# Stepper-Driver.net
KiCad netlist of a schematic drawn in EAGLE
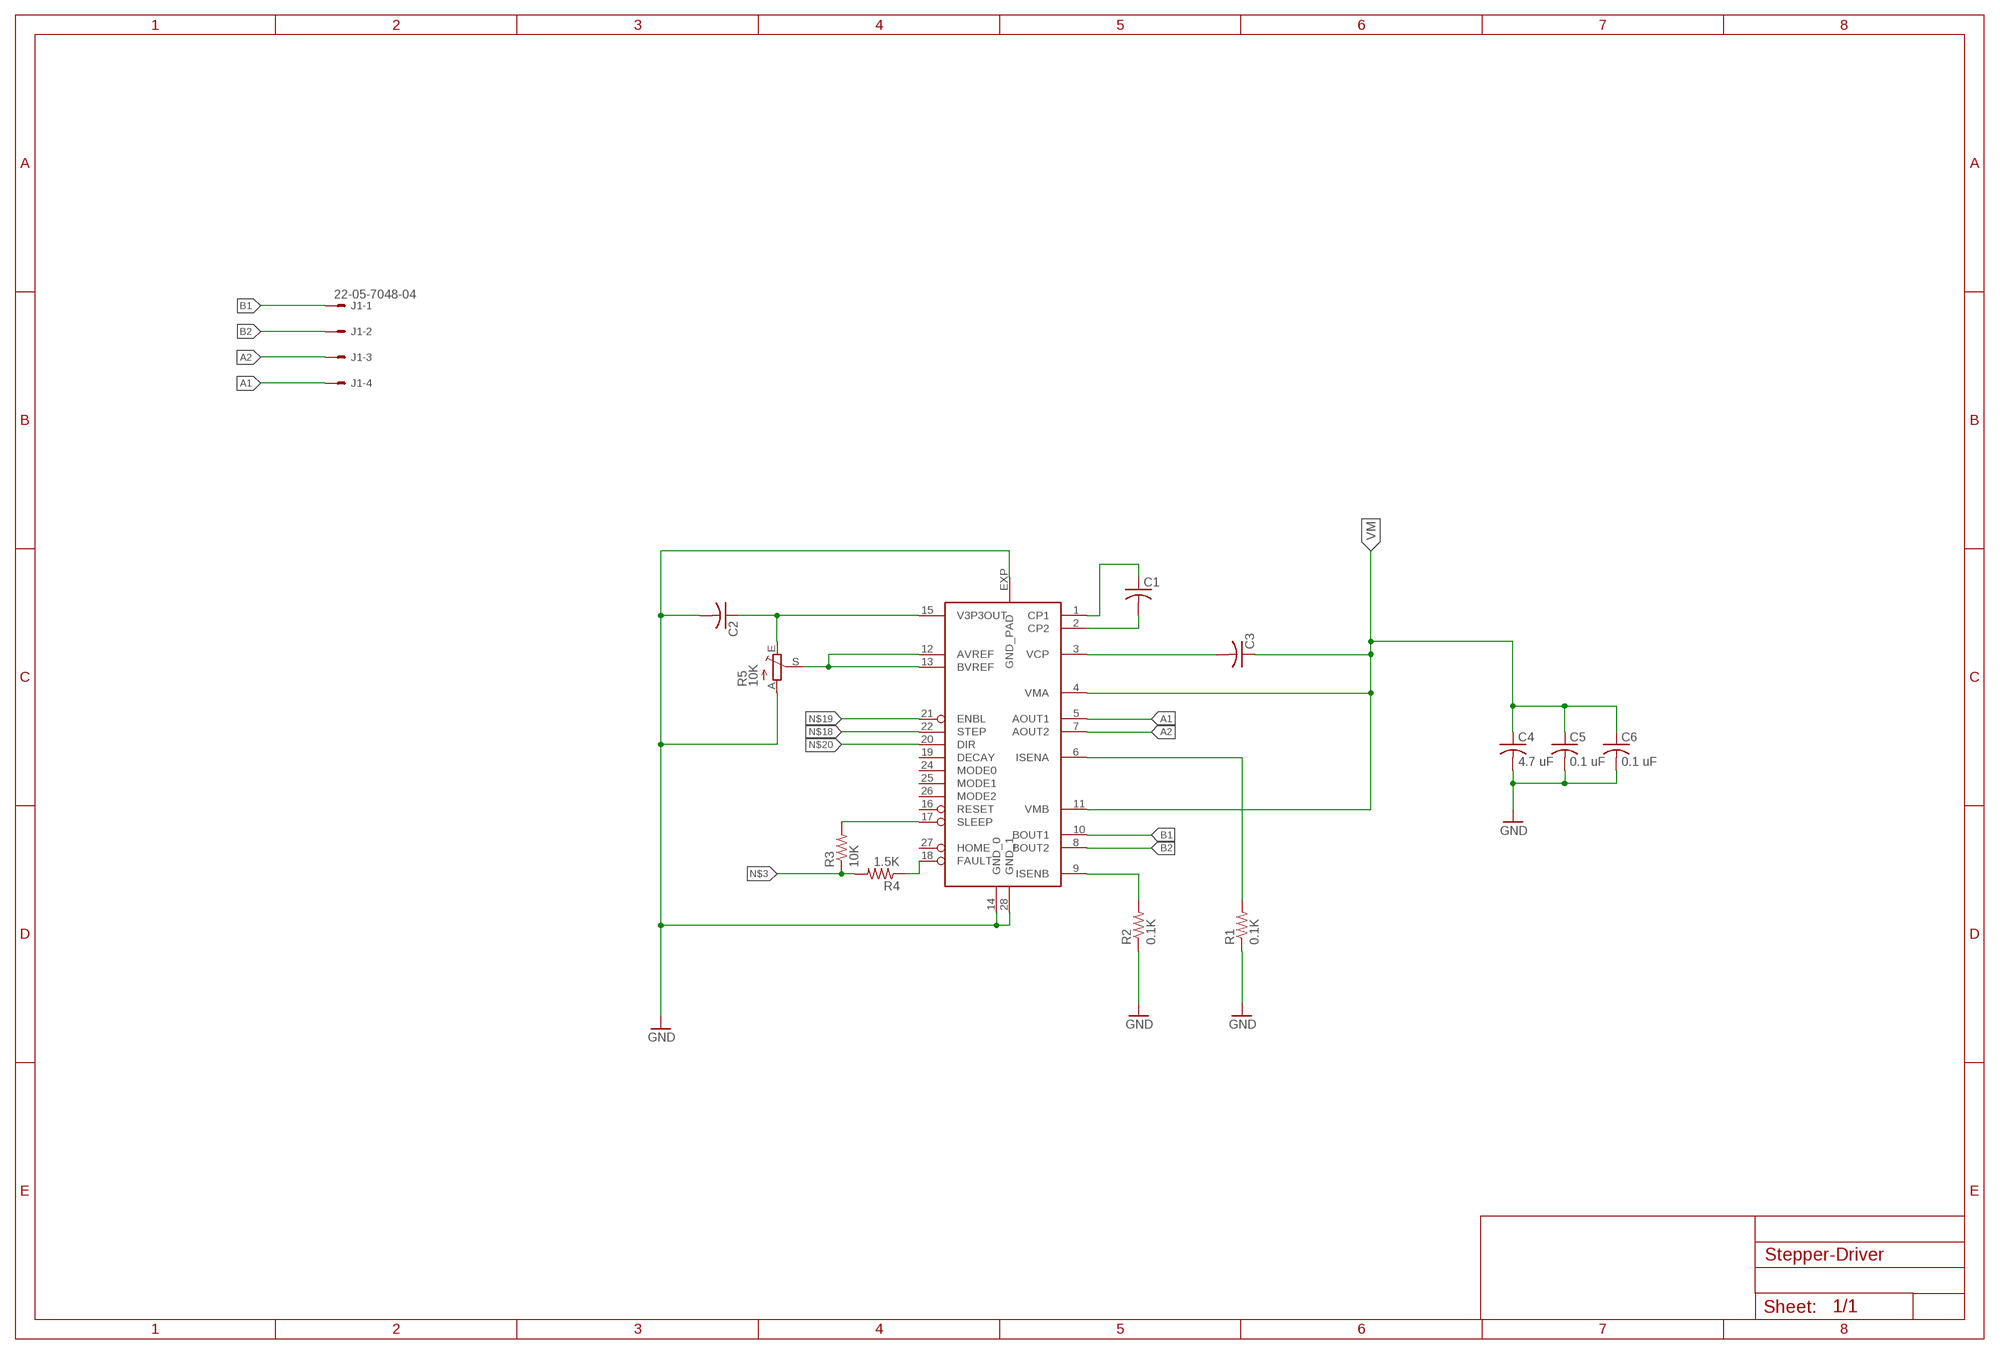
[diagram p0: schematic, sheet 1]

(export (version "E")
  (design (tool "Eeschema 10.0.6"))
  (components
    (comp (ref "C1")
      (value "C-USC0805")
      (footprint "eagle-import:C0805")
      (libsource (lib "eagle-import") (part "C-USC0805"))
    )
    (comp (ref "C2")
      (value "C-USC0805")
      (footprint "eagle-import:C0805")
      (libsource (lib "eagle-import") (part "C-USC0805"))
    )
    (comp (ref "C3")
      (value "C-USC0805")
      (footprint "eagle-import:C0805")
      (libsource (lib "eagle-import") (part "C-USC0805"))
    )
    (comp (ref "C4")
      (value "4.7 uF")
      (footprint "eagle-import:C0805")
      (libsource (lib "eagle-import") (part "C-USC0805"))
    )
    (comp (ref "C5")
      (value "0.1 uF")
      (footprint "eagle-import:C0805")
      (libsource (lib "eagle-import") (part "C-USC0805"))
    )
    (comp (ref "C6")
      (value "0.1 uF")
      (footprint "eagle-import:C0805")
      (libsource (lib "eagle-import") (part "C-USC0805"))
    )
    (comp (ref "J1")
      (value "22-05-7048-04")
      (footprint "eagle-import:7395-04")
      (libsource (lib "eagle-import") (part "22-?-0405-7048"))
    )
    (comp (ref "R1")
      (value "0.1K")
      (footprint "eagle-import:R0805")
      (libsource (lib "eagle-import") (part "R-US_R0805"))
    )
    (comp (ref "R2")
      (value "0.1K")
      (footprint "eagle-import:R0805")
      (libsource (lib "eagle-import") (part "R-US_R0805"))
    )
    (comp (ref "R3")
      (value "10K")
      (footprint "eagle-import:R0805")
      (libsource (lib "eagle-import") (part "R-US_R0805"))
    )
    (comp (ref "R4")
      (value "1.5K")
      (footprint "eagle-import:R0805")
      (libsource (lib "eagle-import") (part "R-US_R0805"))
    )
    (comp (ref "R5")
      (value "10K")
      (footprint "eagle-import:CT6")
      (libsource (lib "eagle-import") (part "TRIM_EU-CT6"))
    )
    (comp (ref "U$1")
      (value "DRV8825PWP")
      (footprint "eagle-import:TSSOP-28")
      (libsource (lib "eagle-import") (part "DRV8825PWP"))
    )
  )
  (nets
    (net (code "1") (name "A1") (class "Default")
      (node (ref "J1") (pin "4") (pinfunction "S_4") (pintype "passive"))
      (node (ref "U$1") (pin "5") (pinfunction "AOUT1_5") (pintype "output"))
    )
    (net (code "2") (name "A2") (class "Default")
      (node (ref "J1") (pin "3") (pinfunction "S_3") (pintype "passive"))
      (node (ref "U$1") (pin "7") (pinfunction "AOUT2_7") (pintype "output"))
    )
    (net (code "3") (name "B1") (class "Default")
      (node (ref "J1") (pin "1") (pinfunction "S_1") (pintype "passive"))
      (node (ref "U$1") (pin "10") (pinfunction "BOUT1_10") (pintype "output"))
    )
    (net (code "4") (name "B2") (class "Default")
      (node (ref "J1") (pin "2") (pinfunction "S_2") (pintype "passive"))
      (node (ref "U$1") (pin "8") (pinfunction "BOUT2_8") (pintype "output"))
    )
    (net (code "5") (name "GND") (class "Default")
      (node (ref "C2") (pin "2") (pinfunction "2_2") (pintype "passive"))
      (node (ref "C4") (pin "2") (pinfunction "2_2") (pintype "passive"))
      (node (ref "C5") (pin "2") (pinfunction "2_2") (pintype "passive"))
      (node (ref "C6") (pin "2") (pinfunction "2_2") (pintype "passive"))
      (node (ref "R1") (pin "1") (pinfunction "1_1") (pintype "passive"))
      (node (ref "R2") (pin "1") (pinfunction "1_1") (pintype "passive"))
      (node (ref "R5") (pin "A") (pinfunction "A_A") (pintype "passive"))
      (node (ref "U$1") (pin "14") (pinfunction "GND_0_14") (pintype "power_in"))
      (node (ref "U$1") (pin "28") (pinfunction "GND_1_28") (pintype "power_in"))
      (node (ref "U$1") (pin "EXP") (pinfunction "GND_PAD_EXP") (pintype "power_in"))
    )
    (net (code "6") (name "N$3") (class "Default")
      (node (ref "R3") (pin "1") (pinfunction "1_1") (pintype "passive"))
      (node (ref "R4") (pin "2") (pinfunction "2_2") (pintype "passive"))
    )
    (net (code "7") (name "N$18") (class "Default")
      (node (ref "U$1") (pin "22") (pinfunction "STEP_22") (pintype "input"))
    )
    (net (code "8") (name "N$19") (class "Default")
      (node (ref "U$1") (pin "21") (pinfunction "ENBL_21") (pintype "input"))
    )
    (net (code "9") (name "N$20") (class "Default")
      (node (ref "U$1") (pin "20") (pinfunction "DIR_20") (pintype "input"))
    )
    (net (code "10") (name "Net-(U$1-AVREF)") (class "Default")
      (node (ref "R5") (pin "S") (pinfunction "S_S") (pintype "passive"))
      (node (ref "U$1") (pin "12") (pinfunction "AVREF_12") (pintype "input"))
      (node (ref "U$1") (pin "13") (pinfunction "BVREF_13") (pintype "input"))
    )
    (net (code "11") (name "Net-(U$1-CP1)") (class "Default")
      (node (ref "C1") (pin "1") (pinfunction "1_1") (pintype "passive"))
      (node (ref "U$1") (pin "1") (pinfunction "CP1_1") (pintype "bidirectional"))
    )
    (net (code "12") (name "Net-(U$1-CP2)") (class "Default")
      (node (ref "C1") (pin "2") (pinfunction "2_2") (pintype "passive"))
      (node (ref "U$1") (pin "2") (pinfunction "CP2_2") (pintype "bidirectional"))
    )
    (net (code "13") (name "Net-(U$1-FAULT)") (class "Default")
      (node (ref "R4") (pin "1") (pinfunction "1_1") (pintype "passive"))
      (node (ref "U$1") (pin "18") (pinfunction "FAULT_18") (pintype "output"))
    )
    (net (code "14") (name "Net-(U$1-ISENA)") (class "Default")
      (node (ref "R1") (pin "2") (pinfunction "2_2") (pintype "passive"))
      (node (ref "U$1") (pin "6") (pinfunction "ISENA_6") (pintype "output"))
    )
    (net (code "15") (name "Net-(U$1-ISENB)") (class "Default")
      (node (ref "R2") (pin "2") (pinfunction "2_2") (pintype "passive"))
      (node (ref "U$1") (pin "9") (pinfunction "ISENB_9") (pintype "output"))
    )
    (net (code "16") (name "Net-(U$1-SLEEP)") (class "Default")
      (node (ref "R3") (pin "2") (pinfunction "2_2") (pintype "passive"))
      (node (ref "U$1") (pin "17") (pinfunction "SLEEP_17") (pintype "input"))
    )
    (net (code "17") (name "Net-(U$1-V3P3OUT)") (class "Default")
      (node (ref "C2") (pin "1") (pinfunction "1_1") (pintype "passive"))
      (node (ref "R5") (pin "E") (pinfunction "E_E") (pintype "passive"))
      (node (ref "U$1") (pin "15") (pinfunction "V3P3OUT_15") (pintype "output"))
    )
    (net (code "18") (name "Net-(U$1-VCP)") (class "Default")
      (node (ref "C3") (pin "2") (pinfunction "2_2") (pintype "passive"))
      (node (ref "U$1") (pin "3") (pinfunction "VCP_3") (pintype "bidirectional"))
    )
    (net (code "19") (name "VM") (class "Default")
      (node (ref "C3") (pin "1") (pinfunction "1_1") (pintype "passive"))
      (node (ref "C4") (pin "1") (pinfunction "1_1") (pintype "passive"))
      (node (ref "C5") (pin "1") (pinfunction "1_1") (pintype "passive"))
      (node (ref "C6") (pin "1") (pinfunction "1_1") (pintype "passive"))
      (node (ref "U$1") (pin "11") (pinfunction "VMB_11") (pintype "power_in"))
      (node (ref "U$1") (pin "4") (pinfunction "VMA_4") (pintype "power_in"))
    )
    (net (code "20") (name "unconnected-(U$1-DECAY-Pad19)") (class "Default")
      (node (ref "U$1") (pin "19") (pinfunction "DECAY_19") (pintype "input"))
    )
    (net (code "21") (name "unconnected-(U$1-HOME-Pad27)") (class "Default")
      (node (ref "U$1") (pin "27") (pinfunction "HOME_27") (pintype "output"))
    )
    (net (code "22") (name "unconnected-(U$1-MODE0-Pad24)") (class "Default")
      (node (ref "U$1") (pin "24") (pinfunction "MODE0_24") (pintype "input"))
    )
    (net (code "23") (name "unconnected-(U$1-MODE1-Pad25)") (class "Default")
      (node (ref "U$1") (pin "25") (pinfunction "MODE1_25") (pintype "input"))
    )
    (net (code "24") (name "unconnected-(U$1-MODE2-Pad26)") (class "Default")
      (node (ref "U$1") (pin "26") (pinfunction "MODE2_26") (pintype "input"))
    )
    (net (code "25") (name "unconnected-(U$1-RESET-Pad16)") (class "Default")
      (node (ref "U$1") (pin "16") (pinfunction "RESET_16") (pintype "input"))
    )
  )
)
